# W050B.net
KiCad netlist of a schematic drawn in EAGLE
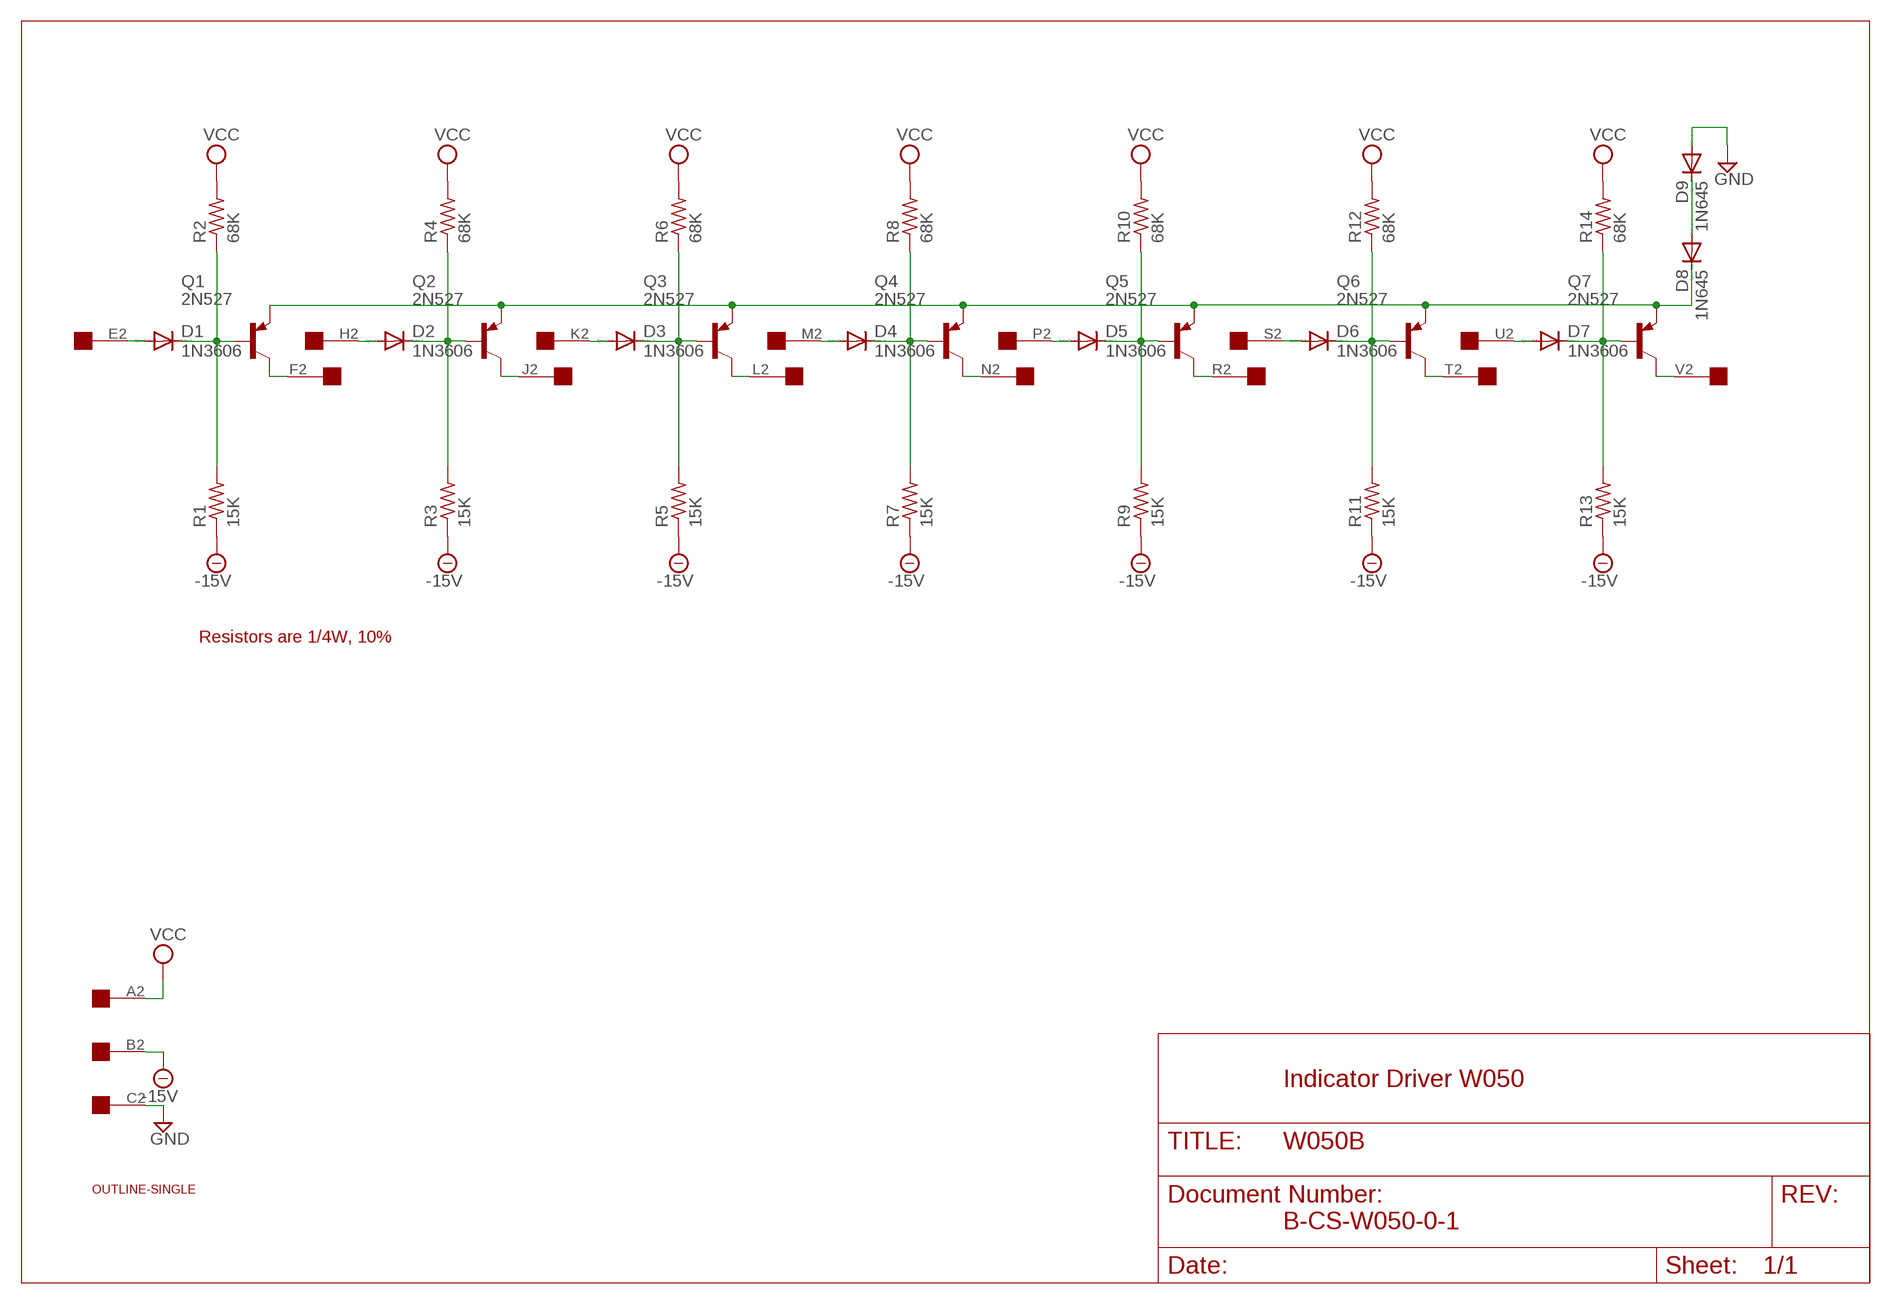
[diagram p0: schematic, sheet 1]

(export (version "E")
  (design (tool "Eeschema 10.0.6"))
  (components
    (comp (ref "D1")
      (value "1N3606")
      (footprint "eagle-import:DO35-10")
      (libsource (lib "eagle-import") (part "DIODE-DO35-10"))
    )
    (comp (ref "D2")
      (value "1N3606")
      (footprint "eagle-import:DO35-10")
      (libsource (lib "eagle-import") (part "DIODE-DO35-10"))
    )
    (comp (ref "D3")
      (value "1N3606")
      (footprint "eagle-import:DO35-10")
      (libsource (lib "eagle-import") (part "DIODE-DO35-10"))
    )
    (comp (ref "D4")
      (value "1N3606")
      (footprint "eagle-import:DO35-10")
      (libsource (lib "eagle-import") (part "DIODE-DO35-10"))
    )
    (comp (ref "D5")
      (value "1N3606")
      (footprint "eagle-import:DO35-10")
      (libsource (lib "eagle-import") (part "DIODE-DO35-10"))
    )
    (comp (ref "D6")
      (value "1N3606")
      (footprint "eagle-import:DO35-10")
      (libsource (lib "eagle-import") (part "DIODE-DO35-10"))
    )
    (comp (ref "D7")
      (value "1N3606")
      (footprint "eagle-import:DO35-10")
      (libsource (lib "eagle-import") (part "DIODE-DO35-10"))
    )
    (comp (ref "D8")
      (value "1N645")
      (footprint "eagle-import:DO35-10")
      (libsource (lib "eagle-import") (part "1N4148DO35-10"))
    )
    (comp (ref "D9")
      (value "1N645")
      (footprint "eagle-import:DO35-10")
      (libsource (lib "eagle-import") (part "1N4148DO35-10"))
    )
    (comp (ref "EDGE")
      (value "EDGE-1")
      (footprint "eagle-import:EDGE-CON1")
      (libsource (lib "eagle-import") (part "EDGE-1"))
    )
    (comp (ref "Q1")
      (value "2N527")
      (footprint "eagle-import:TO39")
      (libsource (lib "eagle-import") (part "2N2904"))
    )
    (comp (ref "Q2")
      (value "2N527")
      (footprint "eagle-import:TO39")
      (libsource (lib "eagle-import") (part "2N2904"))
    )
    (comp (ref "Q3")
      (value "2N527")
      (footprint "eagle-import:TO39")
      (libsource (lib "eagle-import") (part "2N2904"))
    )
    (comp (ref "Q4")
      (value "2N527")
      (footprint "eagle-import:TO39")
      (libsource (lib "eagle-import") (part "2N2904"))
    )
    (comp (ref "Q5")
      (value "2N527")
      (footprint "eagle-import:TO39")
      (libsource (lib "eagle-import") (part "2N2904"))
    )
    (comp (ref "Q6")
      (value "2N527")
      (footprint "eagle-import:TO39")
      (libsource (lib "eagle-import") (part "2N2904"))
    )
    (comp (ref "Q7")
      (value "2N527")
      (footprint "eagle-import:TO39")
      (libsource (lib "eagle-import") (part "2N2904"))
    )
    (comp (ref "R1")
      (value "15K")
      (footprint "eagle-import:0207_10")
      (libsource (lib "eagle-import") (part "R-US_0207/10"))
    )
    (comp (ref "R2")
      (value "68K")
      (footprint "eagle-import:0207_10")
      (libsource (lib "eagle-import") (part "R-US_0207/10"))
    )
    (comp (ref "R3")
      (value "15K")
      (footprint "eagle-import:0207_10")
      (libsource (lib "eagle-import") (part "R-US_0207/10"))
    )
    (comp (ref "R4")
      (value "68K")
      (footprint "eagle-import:0207_10")
      (libsource (lib "eagle-import") (part "R-US_0207/10"))
    )
    (comp (ref "R5")
      (value "15K")
      (footprint "eagle-import:0207_10")
      (libsource (lib "eagle-import") (part "R-US_0207/10"))
    )
    (comp (ref "R6")
      (value "68K")
      (footprint "eagle-import:0207_10")
      (libsource (lib "eagle-import") (part "R-US_0207/10"))
    )
    (comp (ref "R7")
      (value "15K")
      (footprint "eagle-import:0207_10")
      (libsource (lib "eagle-import") (part "R-US_0207/10"))
    )
    (comp (ref "R8")
      (value "68K")
      (footprint "eagle-import:0207_10")
      (libsource (lib "eagle-import") (part "R-US_0207/10"))
    )
    (comp (ref "R9")
      (value "15K")
      (footprint "eagle-import:0207_10")
      (libsource (lib "eagle-import") (part "R-US_0207/10"))
    )
    (comp (ref "R10")
      (value "68K")
      (footprint "eagle-import:0207_10")
      (libsource (lib "eagle-import") (part "R-US_0207/10"))
    )
    (comp (ref "R11")
      (value "15K")
      (footprint "eagle-import:0207_10")
      (libsource (lib "eagle-import") (part "R-US_0207/10"))
    )
    (comp (ref "R12")
      (value "68K")
      (footprint "eagle-import:0207_10")
      (libsource (lib "eagle-import") (part "R-US_0207/10"))
    )
    (comp (ref "R13")
      (value "15K")
      (footprint "eagle-import:0207_10")
      (libsource (lib "eagle-import") (part "R-US_0207/10"))
    )
    (comp (ref "R14")
      (value "68K")
      (footprint "eagle-import:0207_10")
      (libsource (lib "eagle-import") (part "R-US_0207/10"))
    )
    (comp (ref "U$1")
      (value "OUTLINE-SINGLE")
      (footprint "eagle-import:SINGLE")
      (libsource (lib "eagle-import") (part "OUTLINE-SINGLE"))
    )
  )
  (nets
    (net (code "1") (name "-15V") (class "Default")
      (node (ref "EDGE") (pin "B2") (pinfunction "1_B2") (pintype "bidirectional"))
      (node (ref "R1") (pin "1") (pinfunction "1_1") (pintype "passive"))
      (node (ref "R11") (pin "1") (pinfunction "1_1") (pintype "passive"))
      (node (ref "R13") (pin "1") (pinfunction "1_1") (pintype "passive"))
      (node (ref "R3") (pin "1") (pinfunction "1_1") (pintype "passive"))
      (node (ref "R5") (pin "1") (pinfunction "1_1") (pintype "passive"))
      (node (ref "R7") (pin "1") (pinfunction "1_1") (pintype "passive"))
      (node (ref "R9") (pin "1") (pinfunction "1_1") (pintype "passive"))
    )
    (net (code "2") (name "GND") (class "Default")
      (node (ref "D9") (pin "A") (pinfunction "A_A") (pintype "passive"))
      (node (ref "EDGE") (pin "C2") (pinfunction "1_C2") (pintype "bidirectional"))
    )
    (net (code "3") (name "Net-(D8-PadA)") (class "Default")
      (node (ref "D8") (pin "A") (pinfunction "A_A") (pintype "passive"))
      (node (ref "D9") (pin "C") (pinfunction "C_C") (pintype "passive"))
    )
    (net (code "4") (name "Net-(EDGEE-1)") (class "Default")
      (node (ref "D1") (pin "A") (pinfunction "A_A") (pintype "passive"))
      (node (ref "EDGE") (pin "E2") (pinfunction "1_E2") (pintype "bidirectional"))
    )
    (net (code "5") (name "Net-(EDGEF-1)") (class "Default")
      (node (ref "EDGE") (pin "F2") (pinfunction "1_F2") (pintype "bidirectional"))
      (node (ref "Q1") (pin "3") (pinfunction "C_3") (pintype "passive"))
    )
    (net (code "6") (name "Net-(EDGEG-1)") (class "Default")
      (node (ref "D2") (pin "A") (pinfunction "A_A") (pintype "passive"))
      (node (ref "EDGE") (pin "H2") (pinfunction "1_H2") (pintype "bidirectional"))
    )
    (net (code "7") (name "Net-(EDGEH-1)") (class "Default")
      (node (ref "EDGE") (pin "J2") (pinfunction "1_J2") (pintype "bidirectional"))
      (node (ref "Q2") (pin "3") (pinfunction "C_3") (pintype "passive"))
    )
    (net (code "8") (name "Net-(EDGEI-1)") (class "Default")
      (node (ref "D3") (pin "A") (pinfunction "A_A") (pintype "passive"))
      (node (ref "EDGE") (pin "K2") (pinfunction "1_K2") (pintype "bidirectional"))
    )
    (net (code "9") (name "Net-(EDGEJ-1)") (class "Default")
      (node (ref "EDGE") (pin "L2") (pinfunction "1_L2") (pintype "bidirectional"))
      (node (ref "Q3") (pin "3") (pinfunction "C_3") (pintype "passive"))
    )
    (net (code "10") (name "Net-(EDGEK-1)") (class "Default")
      (node (ref "D4") (pin "A") (pinfunction "A_A") (pintype "passive"))
      (node (ref "EDGE") (pin "M2") (pinfunction "1_M2") (pintype "bidirectional"))
    )
    (net (code "11") (name "Net-(EDGEL-1)") (class "Default")
      (node (ref "EDGE") (pin "N2") (pinfunction "1_N2") (pintype "bidirectional"))
      (node (ref "Q4") (pin "3") (pinfunction "C_3") (pintype "passive"))
    )
    (net (code "12") (name "Net-(EDGEM-1)") (class "Default")
      (node (ref "D5") (pin "A") (pinfunction "A_A") (pintype "passive"))
      (node (ref "EDGE") (pin "P2") (pinfunction "1_P2") (pintype "bidirectional"))
    )
    (net (code "13") (name "Net-(EDGEN-1)") (class "Default")
      (node (ref "EDGE") (pin "R2") (pinfunction "1_R2") (pintype "bidirectional"))
      (node (ref "Q5") (pin "3") (pinfunction "C_3") (pintype "passive"))
    )
    (net (code "14") (name "Net-(EDGEO-1)") (class "Default")
      (node (ref "D6") (pin "A") (pinfunction "A_A") (pintype "passive"))
      (node (ref "EDGE") (pin "S2") (pinfunction "1_S2") (pintype "bidirectional"))
    )
    (net (code "15") (name "Net-(EDGEP-1)") (class "Default")
      (node (ref "EDGE") (pin "T2") (pinfunction "1_T2") (pintype "bidirectional"))
      (node (ref "Q6") (pin "3") (pinfunction "C_3") (pintype "passive"))
    )
    (net (code "16") (name "Net-(EDGEQ-1)") (class "Default")
      (node (ref "D7") (pin "A") (pinfunction "A_A") (pintype "passive"))
      (node (ref "EDGE") (pin "U2") (pinfunction "1_U2") (pintype "bidirectional"))
    )
    (net (code "17") (name "Net-(EDGER-1)") (class "Default")
      (node (ref "EDGE") (pin "V2") (pinfunction "1_V2") (pintype "bidirectional"))
      (node (ref "Q7") (pin "3") (pinfunction "C_3") (pintype "passive"))
    )
    (net (code "18") (name "Net-(Q1-B)") (class "Default")
      (node (ref "D1") (pin "C") (pinfunction "C_C") (pintype "passive"))
      (node (ref "Q1") (pin "2") (pinfunction "B_2") (pintype "passive"))
      (node (ref "R1") (pin "2") (pinfunction "2_2") (pintype "passive"))
      (node (ref "R2") (pin "1") (pinfunction "1_1") (pintype "passive"))
    )
    (net (code "19") (name "Net-(Q1-E)") (class "Default")
      (node (ref "D8") (pin "C") (pinfunction "C_C") (pintype "passive"))
      (node (ref "Q1") (pin "1") (pinfunction "E_1") (pintype "passive"))
      (node (ref "Q2") (pin "1") (pinfunction "E_1") (pintype "passive"))
      (node (ref "Q3") (pin "1") (pinfunction "E_1") (pintype "passive"))
      (node (ref "Q4") (pin "1") (pinfunction "E_1") (pintype "passive"))
      (node (ref "Q5") (pin "1") (pinfunction "E_1") (pintype "passive"))
      (node (ref "Q6") (pin "1") (pinfunction "E_1") (pintype "passive"))
      (node (ref "Q7") (pin "1") (pinfunction "E_1") (pintype "passive"))
    )
    (net (code "20") (name "Net-(Q2-B)") (class "Default")
      (node (ref "D2") (pin "C") (pinfunction "C_C") (pintype "passive"))
      (node (ref "Q2") (pin "2") (pinfunction "B_2") (pintype "passive"))
      (node (ref "R3") (pin "2") (pinfunction "2_2") (pintype "passive"))
      (node (ref "R4") (pin "1") (pinfunction "1_1") (pintype "passive"))
    )
    (net (code "21") (name "Net-(Q3-B)") (class "Default")
      (node (ref "D3") (pin "C") (pinfunction "C_C") (pintype "passive"))
      (node (ref "Q3") (pin "2") (pinfunction "B_2") (pintype "passive"))
      (node (ref "R5") (pin "2") (pinfunction "2_2") (pintype "passive"))
      (node (ref "R6") (pin "1") (pinfunction "1_1") (pintype "passive"))
    )
    (net (code "22") (name "Net-(Q4-B)") (class "Default")
      (node (ref "D4") (pin "C") (pinfunction "C_C") (pintype "passive"))
      (node (ref "Q4") (pin "2") (pinfunction "B_2") (pintype "passive"))
      (node (ref "R7") (pin "2") (pinfunction "2_2") (pintype "passive"))
      (node (ref "R8") (pin "1") (pinfunction "1_1") (pintype "passive"))
    )
    (net (code "23") (name "Net-(Q5-B)") (class "Default")
      (node (ref "D5") (pin "C") (pinfunction "C_C") (pintype "passive"))
      (node (ref "Q5") (pin "2") (pinfunction "B_2") (pintype "passive"))
      (node (ref "R10") (pin "1") (pinfunction "1_1") (pintype "passive"))
      (node (ref "R9") (pin "2") (pinfunction "2_2") (pintype "passive"))
    )
    (net (code "24") (name "Net-(Q6-B)") (class "Default")
      (node (ref "D6") (pin "C") (pinfunction "C_C") (pintype "passive"))
      (node (ref "Q6") (pin "2") (pinfunction "B_2") (pintype "passive"))
      (node (ref "R11") (pin "2") (pinfunction "2_2") (pintype "passive"))
      (node (ref "R12") (pin "1") (pinfunction "1_1") (pintype "passive"))
    )
    (net (code "25") (name "Net-(Q7-B)") (class "Default")
      (node (ref "D7") (pin "C") (pinfunction "C_C") (pintype "passive"))
      (node (ref "Q7") (pin "2") (pinfunction "B_2") (pintype "passive"))
      (node (ref "R13") (pin "2") (pinfunction "2_2") (pintype "passive"))
      (node (ref "R14") (pin "1") (pinfunction "1_1") (pintype "passive"))
    )
    (net (code "26") (name "VCC") (class "Default")
      (node (ref "EDGE") (pin "A2") (pinfunction "1_A2") (pintype "bidirectional"))
      (node (ref "R10") (pin "2") (pinfunction "2_2") (pintype "passive"))
      (node (ref "R12") (pin "2") (pinfunction "2_2") (pintype "passive"))
      (node (ref "R14") (pin "2") (pinfunction "2_2") (pintype "passive"))
      (node (ref "R2") (pin "2") (pinfunction "2_2") (pintype "passive"))
      (node (ref "R4") (pin "2") (pinfunction "2_2") (pintype "passive"))
      (node (ref "R6") (pin "2") (pinfunction "2_2") (pintype "passive"))
      (node (ref "R8") (pin "2") (pinfunction "2_2") (pintype "passive"))
    )
  )
)
